# knittykitty.net
KiCad netlist of a schematic drawn in EAGLE
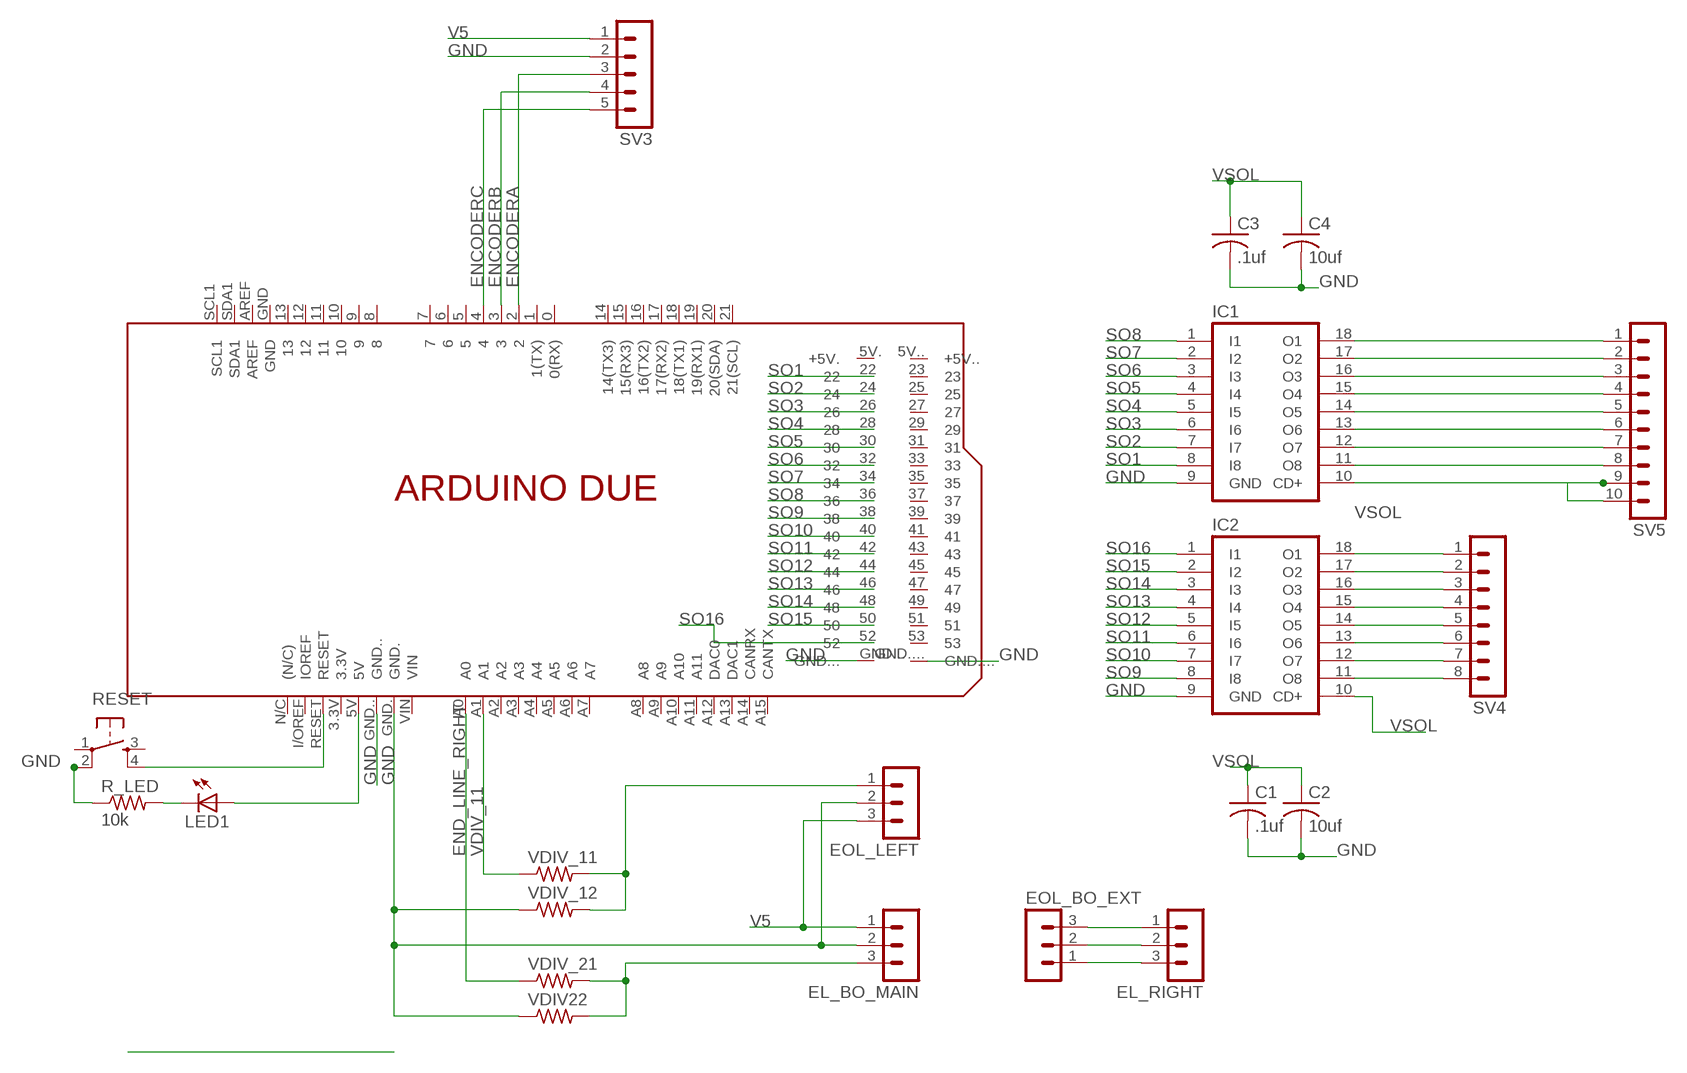
[diagram p0: schematic, sheet 1]

(export (version "E")
  (design (tool "Eeschema 10.0.6"))
  (components
    (comp (ref "C1")
      (value ".1uf")
      (footprint "eagle-import:C1206")
      (libsource (lib "eagle-import") (part "C-USC1206"))
    )
    (comp (ref "C2")
      (value "10uf")
      (footprint "eagle-import:C1206")
      (libsource (lib "eagle-import") (part "C-USC1206"))
    )
    (comp (ref "C3")
      (value ".1uf")
      (footprint "eagle-import:C1206")
      (libsource (lib "eagle-import") (part "C-USC1206"))
    )
    (comp (ref "C4")
      (value "10uf")
      (footprint "eagle-import:C1206")
      (libsource (lib "eagle-import") (part "C-USC1206"))
    )
    (comp (ref "EL_BO_MAIN")
      (value "MA03-1")
      (footprint "eagle-import:MA03-1")
      (libsource (lib "eagle-import") (part "MA03-1"))
    )
    (comp (ref "EL_RIGHT")
      (value "MA03-1")
      (footprint "eagle-import:MA03-1")
      (libsource (lib "eagle-import") (part "MA03-1"))
    )
    (comp (ref "EOL_BO_EXT")
      (value "MA03-1")
      (footprint "eagle-import:MA03-1")
      (libsource (lib "eagle-import") (part "MA03-1"))
    )
    (comp (ref "EOL_LEFT")
      (value "MA03-1")
      (footprint "eagle-import:MA03-1")
      (libsource (lib "eagle-import") (part "MA03-1"))
    )
    (comp (ref "IC1")
      (value "ULN2803ASO")
      (footprint "eagle-import:SO18W")
      (libsource (lib "eagle-import") (part "ULN2803ASO"))
    )
    (comp (ref "IC2")
      (value "ULN2803ASO")
      (footprint "eagle-import:SO18W")
      (libsource (lib "eagle-import") (part "ULN2803ASO"))
    )
    (comp (ref "LED1")
      (value "LEDSMT1206")
      (footprint "eagle-import:1206")
      (libsource (lib "eagle-import") (part "LEDSMT1206"))
    )
    (comp (ref "PCB1")
      (value "ARDUINO_DUE_MIN")
      (footprint "eagle-import:ARDUINO_DUE_MIN")
      (libsource (lib "eagle-import") (part "ARDUINO_DUE_MIN"))
    )
    (comp (ref "RESET")
      (value "6MM_SWITCH6MM_SWITCH")
      (footprint "eagle-import:6MM_SWITCH")
      (libsource (lib "eagle-import") (part "6MM_SWITCH6MM_SWITCH"))
    )
    (comp (ref "R_LED")
      (value "10k")
      (footprint "eagle-import:R1206FAB")
      (libsource (lib "eagle-import") (part "RES-US1206FAB"))
    )
    (comp (ref "SV3")
      (value "MA05-1")
      (footprint "eagle-import:MA05-1")
      (libsource (lib "eagle-import") (part "MA05-1"))
    )
    (comp (ref "SV4")
      (value "MA08-1")
      (footprint "eagle-import:MA08-1")
      (libsource (lib "eagle-import") (part "MA08-1"))
    )
    (comp (ref "SV5")
      (value "MA10-1")
      (footprint "eagle-import:MA10-1")
      (libsource (lib "eagle-import") (part "MA10-1"))
    )
    (comp (ref "VDIV22")
      (value "R-US_R1206")
      (footprint "eagle-import:R1206")
      (libsource (lib "eagle-import") (part "R-US_R1206"))
    )
    (comp (ref "VDIV_11")
      (value "R-US_R1206")
      (footprint "eagle-import:R1206")
      (libsource (lib "eagle-import") (part "R-US_R1206"))
    )
    (comp (ref "VDIV_12")
      (value "R-US_R1206")
      (footprint "eagle-import:R1206")
      (libsource (lib "eagle-import") (part "R-US_R1206"))
    )
    (comp (ref "VDIV_21")
      (value "R-US_R1206")
      (footprint "eagle-import:R1206")
      (libsource (lib "eagle-import") (part "R-US_R1206"))
    )
  )
  (nets
    (net (code "1") (name "/ENCODERA") (class "Default")
      (node (ref "PCB1") (pin "2") (pinfunction "2_2") (pintype "bidirectional"))
      (node (ref "SV3") (pin "3") (pinfunction "3_3") (pintype "passive"))
    )
    (net (code "2") (name "/ENCODERB") (class "Default")
      (node (ref "PCB1") (pin "3") (pinfunction "3_3") (pintype "bidirectional"))
      (node (ref "SV3") (pin "4") (pinfunction "4_4") (pintype "passive"))
    )
    (net (code "3") (name "/ENCODERC") (class "Default")
      (node (ref "PCB1") (pin "4") (pinfunction "4_4") (pintype "bidirectional"))
      (node (ref "SV3") (pin "5") (pinfunction "5_5") (pintype "passive"))
    )
    (net (code "4") (name "/END_LINE_RIGHT") (class "Default")
      (node (ref "PCB1") (pin "A0") (pinfunction "A0_A0") (pintype "bidirectional"))
      (node (ref "VDIV_21") (pin "1") (pinfunction "1_1") (pintype "passive"))
    )
    (net (code "5") (name "/GND") (class "Default")
      (node (ref "C1") (pin "2") (pinfunction "2_2") (pintype "passive"))
      (node (ref "C2") (pin "2") (pinfunction "2_2") (pintype "passive"))
      (node (ref "C3") (pin "2") (pinfunction "2_2") (pintype "passive"))
      (node (ref "C4") (pin "2") (pinfunction "2_2") (pintype "passive"))
      (node (ref "EL_BO_MAIN") (pin "2") (pinfunction "2_2") (pintype "passive"))
      (node (ref "EOL_LEFT") (pin "2") (pinfunction "2_2") (pintype "passive"))
      (node (ref "IC1") (pin "9") (pinfunction "GND_9") (pintype "power_in"))
      (node (ref "IC2") (pin "9") (pinfunction "GND_9") (pintype "power_in"))
      (node (ref "PCB1") (pin "GND.") (pinfunction "GND._GND.") (pintype "bidirectional"))
      (node (ref "PCB1") (pin "GND..") (pinfunction "GND.._GND..") (pintype "bidirectional"))
      (node (ref "RESET") (pin "2") (pinfunction "P1_2") (pintype "passive"))
      (node (ref "R_LED") (pin "1") (pinfunction "1_1") (pintype "passive"))
      (node (ref "SV3") (pin "2") (pinfunction "2_2") (pintype "passive"))
      (node (ref "VDIV22") (pin "1") (pinfunction "1_1") (pintype "passive"))
      (node (ref "VDIV_12") (pin "1") (pinfunction "1_1") (pintype "passive"))
    )
    (net (code "6") (name "/SO1") (class "Default")
      (node (ref "IC1") (pin "8") (pinfunction "I8_8") (pintype "input"))
      (node (ref "PCB1") (pin "22") (pinfunction "22_22") (pintype "bidirectional"))
    )
    (net (code "7") (name "/SO2") (class "Default")
      (node (ref "IC1") (pin "7") (pinfunction "I7_7") (pintype "input"))
      (node (ref "PCB1") (pin "24") (pinfunction "24_24") (pintype "bidirectional"))
    )
    (net (code "8") (name "/SO3") (class "Default")
      (node (ref "IC1") (pin "6") (pinfunction "I6_6") (pintype "input"))
      (node (ref "PCB1") (pin "26") (pinfunction "26_26") (pintype "bidirectional"))
    )
    (net (code "9") (name "/SO4") (class "Default")
      (node (ref "IC1") (pin "5") (pinfunction "I5_5") (pintype "input"))
      (node (ref "PCB1") (pin "28") (pinfunction "28_28") (pintype "bidirectional"))
    )
    (net (code "10") (name "/SO5") (class "Default")
      (node (ref "IC1") (pin "4") (pinfunction "I4_4") (pintype "input"))
      (node (ref "PCB1") (pin "30") (pinfunction "30_30") (pintype "bidirectional"))
    )
    (net (code "11") (name "/SO6") (class "Default")
      (node (ref "IC1") (pin "3") (pinfunction "I3_3") (pintype "input"))
      (node (ref "PCB1") (pin "32") (pinfunction "32_32") (pintype "bidirectional"))
    )
    (net (code "12") (name "/SO7") (class "Default")
      (node (ref "IC1") (pin "2") (pinfunction "I2_2") (pintype "input"))
      (node (ref "PCB1") (pin "34") (pinfunction "34_34") (pintype "bidirectional"))
    )
    (net (code "13") (name "/SO8") (class "Default")
      (node (ref "IC1") (pin "1") (pinfunction "I1_1") (pintype "input"))
      (node (ref "PCB1") (pin "36") (pinfunction "36_36") (pintype "bidirectional"))
    )
    (net (code "14") (name "/SO9") (class "Default")
      (node (ref "IC2") (pin "8") (pinfunction "I8_8") (pintype "input"))
      (node (ref "PCB1") (pin "38") (pinfunction "38_38") (pintype "bidirectional"))
    )
    (net (code "15") (name "/SO10") (class "Default")
      (node (ref "IC2") (pin "7") (pinfunction "I7_7") (pintype "input"))
      (node (ref "PCB1") (pin "40") (pinfunction "40_40") (pintype "bidirectional"))
    )
    (net (code "16") (name "/SO11") (class "Default")
      (node (ref "IC2") (pin "6") (pinfunction "I6_6") (pintype "input"))
      (node (ref "PCB1") (pin "42") (pinfunction "42_42") (pintype "bidirectional"))
    )
    (net (code "17") (name "/SO12") (class "Default")
      (node (ref "IC2") (pin "5") (pinfunction "I5_5") (pintype "input"))
      (node (ref "PCB1") (pin "44") (pinfunction "44_44") (pintype "bidirectional"))
    )
    (net (code "18") (name "/SO13") (class "Default")
      (node (ref "IC2") (pin "4") (pinfunction "I4_4") (pintype "input"))
      (node (ref "PCB1") (pin "46") (pinfunction "46_46") (pintype "bidirectional"))
    )
    (net (code "19") (name "/SO14") (class "Default")
      (node (ref "IC2") (pin "3") (pinfunction "I3_3") (pintype "input"))
      (node (ref "PCB1") (pin "48") (pinfunction "48_48") (pintype "bidirectional"))
    )
    (net (code "20") (name "/SO15") (class "Default")
      (node (ref "IC2") (pin "2") (pinfunction "I2_2") (pintype "input"))
      (node (ref "PCB1") (pin "50") (pinfunction "50_50") (pintype "bidirectional"))
    )
    (net (code "21") (name "/SO16") (class "Default")
      (node (ref "IC2") (pin "1") (pinfunction "I1_1") (pintype "input"))
      (node (ref "PCB1") (pin "52") (pinfunction "52_52") (pintype "bidirectional"))
    )
    (net (code "22") (name "/V5") (class "Default")
      (node (ref "EL_BO_MAIN") (pin "1") (pinfunction "1_1") (pintype "passive"))
      (node (ref "EOL_LEFT") (pin "3") (pinfunction "3_3") (pintype "passive"))
      (node (ref "LED1") (pin "A") (pinfunction "A_A") (pintype "passive"))
      (node (ref "PCB1") (pin "5V") (pinfunction "5V_5V") (pintype "bidirectional"))
      (node (ref "SV3") (pin "1") (pinfunction "1_1") (pintype "passive"))
    )
    (net (code "23") (name "/VDIV_11") (class "Default")
      (node (ref "PCB1") (pin "A1") (pinfunction "A1_A1") (pintype "bidirectional"))
      (node (ref "VDIV_11") (pin "1") (pinfunction "1_1") (pintype "passive"))
    )
    (net (code "24") (name "/VSOL") (class "Default")
      (node (ref "C1") (pin "1") (pinfunction "1_1") (pintype "passive"))
      (node (ref "C2") (pin "1") (pinfunction "1_1") (pintype "passive"))
      (node (ref "C3") (pin "1") (pinfunction "1_1") (pintype "passive"))
      (node (ref "C4") (pin "1") (pinfunction "1_1") (pintype "passive"))
      (node (ref "IC1") (pin "10") (pinfunction "CD+_10") (pintype "passive"))
      (node (ref "IC2") (pin "10") (pinfunction "CD+_10") (pintype "passive"))
      (node (ref "SV5") (pin "10") (pinfunction "10_10") (pintype "passive"))
      (node (ref "SV5") (pin "9") (pinfunction "9_9") (pintype "passive"))
    )
    (net (code "25") (name "Net-(EL_BO_MAIN-Pad3)") (class "Default")
      (node (ref "EL_BO_MAIN") (pin "3") (pinfunction "3_3") (pintype "passive"))
      (node (ref "VDIV22") (pin "2") (pinfunction "2_2") (pintype "passive"))
      (node (ref "VDIV_21") (pin "2") (pinfunction "2_2") (pintype "passive"))
    )
    (net (code "26") (name "Net-(EL_RIGHT-Pad1)") (class "Default")
      (node (ref "EL_RIGHT") (pin "1") (pinfunction "1_1") (pintype "passive"))
      (node (ref "EOL_BO_EXT") (pin "3") (pinfunction "3_3") (pintype "passive"))
    )
    (net (code "27") (name "Net-(EL_RIGHT-Pad2)") (class "Default")
      (node (ref "EL_RIGHT") (pin "2") (pinfunction "2_2") (pintype "passive"))
      (node (ref "EOL_BO_EXT") (pin "2") (pinfunction "2_2") (pintype "passive"))
    )
    (net (code "28") (name "Net-(EL_RIGHT-Pad3)") (class "Default")
      (node (ref "EL_RIGHT") (pin "3") (pinfunction "3_3") (pintype "passive"))
      (node (ref "EOL_BO_EXT") (pin "1") (pinfunction "1_1") (pintype "passive"))
    )
    (net (code "29") (name "Net-(EOL_LEFT-Pad1)") (class "Default")
      (node (ref "EOL_LEFT") (pin "1") (pinfunction "1_1") (pintype "passive"))
      (node (ref "VDIV_11") (pin "2") (pinfunction "2_2") (pintype "passive"))
      (node (ref "VDIV_12") (pin "2") (pinfunction "2_2") (pintype "passive"))
    )
    (net (code "30") (name "Net-(IC1-O1)") (class "Default")
      (node (ref "IC1") (pin "18") (pinfunction "O1_18") (pintype "open_collector"))
      (node (ref "SV5") (pin "1") (pinfunction "1_1") (pintype "passive"))
    )
    (net (code "31") (name "Net-(IC1-O2)") (class "Default")
      (node (ref "IC1") (pin "17") (pinfunction "O2_17") (pintype "open_collector"))
      (node (ref "SV5") (pin "2") (pinfunction "2_2") (pintype "passive"))
    )
    (net (code "32") (name "Net-(IC1-O3)") (class "Default")
      (node (ref "IC1") (pin "16") (pinfunction "O3_16") (pintype "open_collector"))
      (node (ref "SV5") (pin "3") (pinfunction "3_3") (pintype "passive"))
    )
    (net (code "33") (name "Net-(IC1-O4)") (class "Default")
      (node (ref "IC1") (pin "15") (pinfunction "O4_15") (pintype "open_collector"))
      (node (ref "SV5") (pin "4") (pinfunction "4_4") (pintype "passive"))
    )
    (net (code "34") (name "Net-(IC1-O5)") (class "Default")
      (node (ref "IC1") (pin "14") (pinfunction "O5_14") (pintype "open_collector"))
      (node (ref "SV5") (pin "5") (pinfunction "5_5") (pintype "passive"))
    )
    (net (code "35") (name "Net-(IC1-O6)") (class "Default")
      (node (ref "IC1") (pin "13") (pinfunction "O6_13") (pintype "open_collector"))
      (node (ref "SV5") (pin "6") (pinfunction "6_6") (pintype "passive"))
    )
    (net (code "36") (name "Net-(IC1-O7)") (class "Default")
      (node (ref "IC1") (pin "12") (pinfunction "O7_12") (pintype "open_collector"))
      (node (ref "SV5") (pin "7") (pinfunction "7_7") (pintype "passive"))
    )
    (net (code "37") (name "Net-(IC1-O8)") (class "Default")
      (node (ref "IC1") (pin "11") (pinfunction "O8_11") (pintype "open_collector"))
      (node (ref "SV5") (pin "8") (pinfunction "8_8") (pintype "passive"))
    )
    (net (code "38") (name "Net-(IC2-O1)") (class "Default")
      (node (ref "IC2") (pin "18") (pinfunction "O1_18") (pintype "open_collector"))
      (node (ref "SV4") (pin "1") (pinfunction "1_1") (pintype "passive"))
    )
    (net (code "39") (name "Net-(IC2-O2)") (class "Default")
      (node (ref "IC2") (pin "17") (pinfunction "O2_17") (pintype "open_collector"))
      (node (ref "SV4") (pin "2") (pinfunction "2_2") (pintype "passive"))
    )
    (net (code "40") (name "Net-(IC2-O3)") (class "Default")
      (node (ref "IC2") (pin "16") (pinfunction "O3_16") (pintype "open_collector"))
      (node (ref "SV4") (pin "3") (pinfunction "3_3") (pintype "passive"))
    )
    (net (code "41") (name "Net-(IC2-O4)") (class "Default")
      (node (ref "IC2") (pin "15") (pinfunction "O4_15") (pintype "open_collector"))
      (node (ref "SV4") (pin "4") (pinfunction "4_4") (pintype "passive"))
    )
    (net (code "42") (name "Net-(IC2-O5)") (class "Default")
      (node (ref "IC2") (pin "14") (pinfunction "O5_14") (pintype "open_collector"))
      (node (ref "SV4") (pin "5") (pinfunction "5_5") (pintype "passive"))
    )
    (net (code "43") (name "Net-(IC2-O6)") (class "Default")
      (node (ref "IC2") (pin "13") (pinfunction "O6_13") (pintype "open_collector"))
      (node (ref "SV4") (pin "6") (pinfunction "6_6") (pintype "passive"))
    )
    (net (code "44") (name "Net-(IC2-O7)") (class "Default")
      (node (ref "IC2") (pin "12") (pinfunction "O7_12") (pintype "open_collector"))
      (node (ref "SV4") (pin "7") (pinfunction "7_7") (pintype "passive"))
    )
    (net (code "45") (name "Net-(IC2-O8)") (class "Default")
      (node (ref "IC2") (pin "11") (pinfunction "O8_11") (pintype "open_collector"))
      (node (ref "SV4") (pin "8") (pinfunction "8_8") (pintype "passive"))
    )
    (net (code "46") (name "Net-(LED1-PadC)") (class "Default")
      (node (ref "LED1") (pin "C") (pinfunction "C_C") (pintype "passive"))
      (node (ref "R_LED") (pin "2") (pinfunction "2_2") (pintype "passive"))
    )
    (net (code "47") (name "Net-(RESET-S1)") (class "Default")
      (node (ref "PCB1") (pin "RESET") (pinfunction "RESET_RESET") (pintype "bidirectional"))
      (node (ref "RESET") (pin "4") (pinfunction "S1_4") (pintype "passive"))
    )
    (net (code "48") (name "unconnected-(PCB1-(N{slash}C)-PadN{slash}C)") (class "Default")
      (node (ref "PCB1") (pin "N/C") (pinfunction "(N/C)_N/C") (pintype "bidirectional"))
    )
    (net (code "49") (name "unconnected-(PCB1-+5V.-Pad5V.)") (class "Default")
      (node (ref "PCB1") (pin "5V.") (pinfunction "+5V._5V.") (pintype "bidirectional"))
    )
    (net (code "50") (name "unconnected-(PCB1-+5V..-Pad5V..)") (class "Default")
      (node (ref "PCB1") (pin "5V..") (pinfunction "+5V.._5V..") (pintype "bidirectional"))
    )
    (net (code "51") (name "unconnected-(PCB1-0(RX)-Pad0)") (class "Default")
      (node (ref "PCB1") (pin "0") (pinfunction "0(RX)_0") (pintype "bidirectional"))
    )
    (net (code "52") (name "unconnected-(PCB1-1(TX)-Pad1)") (class "Default")
      (node (ref "PCB1") (pin "1") (pinfunction "1(TX)_1") (pintype "bidirectional"))
    )
    (net (code "53") (name "unconnected-(PCB1-14(TX3)-Pad14)") (class "Default")
      (node (ref "PCB1") (pin "14") (pinfunction "14(TX3)_14") (pintype "bidirectional"))
    )
    (net (code "54") (name "unconnected-(PCB1-15(RX3)-Pad15)") (class "Default")
      (node (ref "PCB1") (pin "15") (pinfunction "15(RX3)_15") (pintype "bidirectional"))
    )
    (net (code "55") (name "unconnected-(PCB1-16(TX2)-Pad16)") (class "Default")
      (node (ref "PCB1") (pin "16") (pinfunction "16(TX2)_16") (pintype "bidirectional"))
    )
    (net (code "56") (name "unconnected-(PCB1-17(RX2)-Pad17)") (class "Default")
      (node (ref "PCB1") (pin "17") (pinfunction "17(RX2)_17") (pintype "bidirectional"))
    )
    (net (code "57") (name "unconnected-(PCB1-18(TX1)-Pad18)") (class "Default")
      (node (ref "PCB1") (pin "18") (pinfunction "18(TX1)_18") (pintype "bidirectional"))
    )
    (net (code "58") (name "unconnected-(PCB1-19(RX1)-Pad19)") (class "Default")
      (node (ref "PCB1") (pin "19") (pinfunction "19(RX1)_19") (pintype "bidirectional"))
    )
    (net (code "59") (name "unconnected-(PCB1-20(SDA)-Pad20)") (class "Default")
      (node (ref "PCB1") (pin "20") (pinfunction "20(SDA)_20") (pintype "bidirectional"))
    )
    (net (code "60") (name "unconnected-(PCB1-21(SCL)-Pad21)") (class "Default")
      (node (ref "PCB1") (pin "21") (pinfunction "21(SCL)_21") (pintype "bidirectional"))
    )
    (net (code "61") (name "unconnected-(PCB1-CANRX-PadA14)") (class "Default")
      (node (ref "PCB1") (pin "A14") (pinfunction "CANRX_A14") (pintype "bidirectional"))
    )
    (net (code "62") (name "unconnected-(PCB1-CANTX-PadA15)") (class "Default")
      (node (ref "PCB1") (pin "A15") (pinfunction "CANTX_A15") (pintype "bidirectional"))
    )
    (net (code "63") (name "unconnected-(PCB1-DAC0-PadA12)") (class "Default")
      (node (ref "PCB1") (pin "A12") (pinfunction "DAC0_A12") (pintype "bidirectional"))
    )
    (net (code "64") (name "unconnected-(PCB1-DAC1-PadA13)") (class "Default")
      (node (ref "PCB1") (pin "A13") (pinfunction "DAC1_A13") (pintype "bidirectional"))
    )
    (net (code "65") (name "unconnected-(PCB1-IOREF-PadI{slash}OREF)") (class "Default")
      (node (ref "PCB1") (pin "I/OREF") (pinfunction "IOREF_I/OREF") (pintype "bidirectional"))
    )
    (net (code "66") (name "unconnected-(PCB1-Pad3.3V)") (class "Default")
      (node (ref "PCB1") (pin "3.3V") (pinfunction "3.3V_3.3V") (pintype "bidirectional"))
    )
    (net (code "67") (name "unconnected-(PCB1-Pad5)") (class "Default")
      (node (ref "PCB1") (pin "5") (pinfunction "5_5") (pintype "bidirectional"))
    )
    (net (code "68") (name "unconnected-(PCB1-Pad6)") (class "Default")
      (node (ref "PCB1") (pin "6") (pinfunction "6_6") (pintype "bidirectional"))
    )
    (net (code "69") (name "unconnected-(PCB1-Pad7)") (class "Default")
      (node (ref "PCB1") (pin "7") (pinfunction "7_7") (pintype "bidirectional"))
    )
    (net (code "70") (name "unconnected-(PCB1-Pad8)") (class "Default")
      (node (ref "PCB1") (pin "8") (pinfunction "8_8") (pintype "bidirectional"))
    )
    (net (code "71") (name "unconnected-(PCB1-Pad9)") (class "Default")
      (node (ref "PCB1") (pin "9") (pinfunction "9_9") (pintype "bidirectional"))
    )
    (net (code "72") (name "unconnected-(PCB1-Pad10)") (class "Default")
      (node (ref "PCB1") (pin "10") (pinfunction "10_10") (pintype "bidirectional"))
    )
    (net (code "73") (name "unconnected-(PCB1-Pad11)") (class "Default")
      (node (ref "PCB1") (pin "11") (pinfunction "11_11") (pintype "bidirectional"))
    )
    (net (code "74") (name "unconnected-(PCB1-Pad12)") (class "Default")
      (node (ref "PCB1") (pin "12") (pinfunction "12_12") (pintype "bidirectional"))
    )
    (net (code "75") (name "unconnected-(PCB1-Pad13)") (class "Default")
      (node (ref "PCB1") (pin "13") (pinfunction "13_13") (pintype "bidirectional"))
    )
    (net (code "76") (name "unconnected-(PCB1-Pad23)") (class "Default")
      (node (ref "PCB1") (pin "23") (pinfunction "23_23") (pintype "bidirectional"))
    )
    (net (code "77") (name "unconnected-(PCB1-Pad25)") (class "Default")
      (node (ref "PCB1") (pin "25") (pinfunction "25_25") (pintype "bidirectional"))
    )
    (net (code "78") (name "unconnected-(PCB1-Pad27)") (class "Default")
      (node (ref "PCB1") (pin "27") (pinfunction "27_27") (pintype "bidirectional"))
    )
    (net (code "79") (name "unconnected-(PCB1-Pad29)") (class "Default")
      (node (ref "PCB1") (pin "29") (pinfunction "29_29") (pintype "bidirectional"))
    )
    (net (code "80") (name "unconnected-(PCB1-Pad31)") (class "Default")
      (node (ref "PCB1") (pin "31") (pinfunction "31_31") (pintype "bidirectional"))
    )
    (net (code "81") (name "unconnected-(PCB1-Pad33)") (class "Default")
      (node (ref "PCB1") (pin "33") (pinfunction "33_33") (pintype "bidirectional"))
    )
    (net (code "82") (name "unconnected-(PCB1-Pad35)") (class "Default")
      (node (ref "PCB1") (pin "35") (pinfunction "35_35") (pintype "bidirectional"))
    )
    (net (code "83") (name "unconnected-(PCB1-Pad37)") (class "Default")
      (node (ref "PCB1") (pin "37") (pinfunction "37_37") (pintype "bidirectional"))
    )
    (net (code "84") (name "unconnected-(PCB1-Pad39)") (class "Default")
      (node (ref "PCB1") (pin "39") (pinfunction "39_39") (pintype "bidirectional"))
    )
    (net (code "85") (name "unconnected-(PCB1-Pad41)") (class "Default")
      (node (ref "PCB1") (pin "41") (pinfunction "41_41") (pintype "bidirectional"))
    )
    (net (code "86") (name "unconnected-(PCB1-Pad43)") (class "Default")
      (node (ref "PCB1") (pin "43") (pinfunction "43_43") (pintype "bidirectional"))
    )
    (net (code "87") (name "unconnected-(PCB1-Pad45)") (class "Default")
      (node (ref "PCB1") (pin "45") (pinfunction "45_45") (pintype "bidirectional"))
    )
    (net (code "88") (name "unconnected-(PCB1-Pad47)") (class "Default")
      (node (ref "PCB1") (pin "47") (pinfunction "47_47") (pintype "bidirectional"))
    )
    (net (code "89") (name "unconnected-(PCB1-Pad49)") (class "Default")
      (node (ref "PCB1") (pin "49") (pinfunction "49_49") (pintype "bidirectional"))
    )
    (net (code "90") (name "unconnected-(PCB1-Pad51)") (class "Default")
      (node (ref "PCB1") (pin "51") (pinfunction "51_51") (pintype "bidirectional"))
    )
    (net (code "91") (name "unconnected-(PCB1-Pad53)") (class "Default")
      (node (ref "PCB1") (pin "53") (pinfunction "53_53") (pintype "bidirectional"))
    )
    (net (code "92") (name "unconnected-(PCB1-PadA2)") (class "Default")
      (node (ref "PCB1") (pin "A2") (pinfunction "A2_A2") (pintype "bidirectional"))
    )
    (net (code "93") (name "unconnected-(PCB1-PadA3)") (class "Default")
      (node (ref "PCB1") (pin "A3") (pinfunction "A3_A3") (pintype "bidirectional"))
    )
    (net (code "94") (name "unconnected-(PCB1-PadA4)") (class "Default")
      (node (ref "PCB1") (pin "A4") (pinfunction "A4_A4") (pintype "bidirectional"))
    )
    (net (code "95") (name "unconnected-(PCB1-PadA5)") (class "Default")
      (node (ref "PCB1") (pin "A5") (pinfunction "A5_A5") (pintype "bidirectional"))
    )
    (net (code "96") (name "unconnected-(PCB1-PadA6)") (class "Default")
      (node (ref "PCB1") (pin "A6") (pinfunction "A6_A6") (pintype "bidirectional"))
    )
    (net (code "97") (name "unconnected-(PCB1-PadA7)") (class "Default")
      (node (ref "PCB1") (pin "A7") (pinfunction "A7_A7") (pintype "bidirectional"))
    )
    (net (code "98") (name "unconnected-(PCB1-PadA8)") (class "Default")
      (node (ref "PCB1") (pin "A8") (pinfunction "A8_A8") (pintype "bidirectional"))
    )
    (net (code "99") (name "unconnected-(PCB1-PadA9)") (class "Default")
      (node (ref "PCB1") (pin "A9") (pinfunction "A9_A9") (pintype "bidirectional"))
    )
    (net (code "100") (name "unconnected-(PCB1-PadA10)") (class "Default")
      (node (ref "PCB1") (pin "A10") (pinfunction "A10_A10") (pintype "bidirectional"))
    )
    (net (code "101") (name "unconnected-(PCB1-PadA11)") (class "Default")
      (node (ref "PCB1") (pin "A11") (pinfunction "A11_A11") (pintype "bidirectional"))
    )
    (net (code "102") (name "unconnected-(PCB1-PadAREF)") (class "Default")
      (node (ref "PCB1") (pin "AREF") (pinfunction "AREF_AREF") (pintype "bidirectional"))
    )
    (net (code "103") (name "unconnected-(PCB1-PadGND)") (class "Default")
      (node (ref "PCB1") (pin "GND") (pinfunction "GND_GND") (pintype "bidirectional"))
    )
    (net (code "104") (name "unconnected-(PCB1-PadGND...)") (class "Default")
      (node (ref "PCB1") (pin "GND...") (pinfunction "GND..._GND...") (pintype "bidirectional"))
    )
    (net (code "105") (name "unconnected-(PCB1-PadGND....)") (class "Default")
      (node (ref "PCB1") (pin "GND....") (pinfunction "GND...._GND....") (pintype "bidirectional"))
    )
    (net (code "106") (name "unconnected-(PCB1-PadSCL1)") (class "Default")
      (node (ref "PCB1") (pin "SCL1") (pinfunction "SCL1_SCL1") (pintype "bidirectional"))
    )
    (net (code "107") (name "unconnected-(PCB1-PadSDA1)") (class "Default")
      (node (ref "PCB1") (pin "SDA1") (pinfunction "SDA1_SDA1") (pintype "bidirectional"))
    )
    (net (code "108") (name "unconnected-(PCB1-PadVIN)") (class "Default")
      (node (ref "PCB1") (pin "VIN") (pinfunction "VIN_VIN") (pintype "bidirectional"))
    )
    (net (code "109") (name "unconnected-(RESET-P-Pad1)") (class "Default")
      (node (ref "RESET") (pin "1") (pinfunction "P_1") (pintype "passive"))
    )
    (net (code "110") (name "unconnected-(RESET-S-Pad3)") (class "Default")
      (node (ref "RESET") (pin "3") (pinfunction "S_3") (pintype "passive"))
    )
  )
)
